# Ref_Supply_Unit.net
KiCad netlist of a schematic drawn in Altium Designer
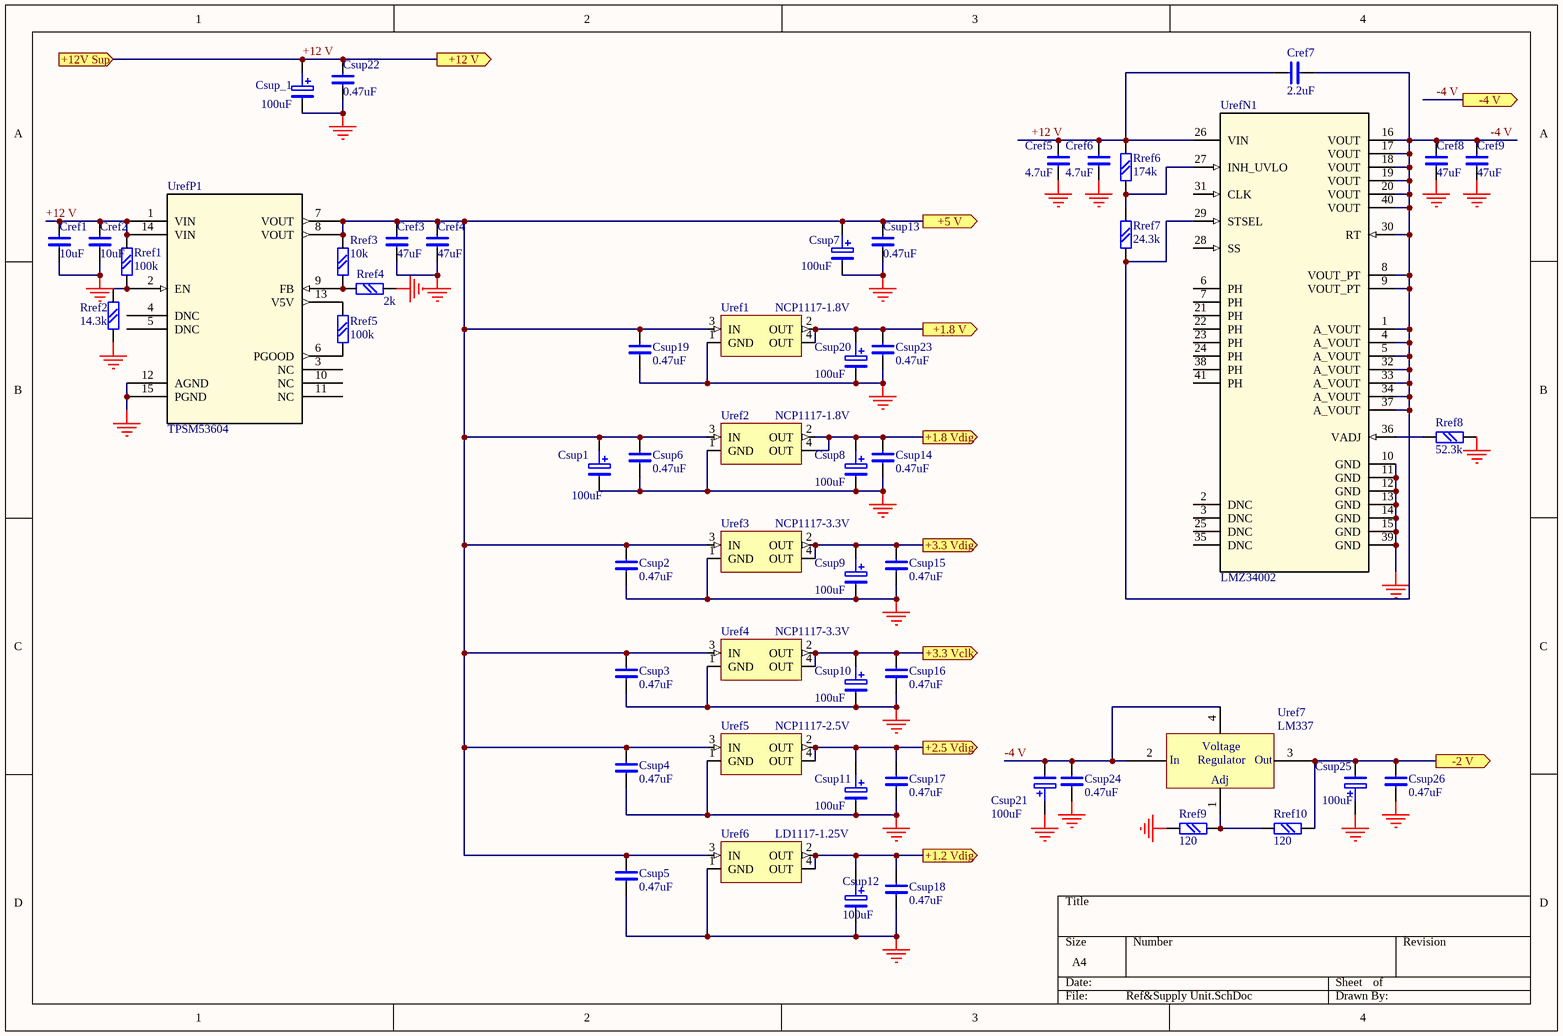
[diagram p0: Ref&Supply Unit.SchDoc]

(export (version "E")
  (design (tool "Eeschema 10.0.6"))
  (components
    (comp (ref "Cref1") (value "10uF") (footprint "CHIP1206") (libsource (lib "*") (part "C")))
    (comp (ref "Cref2") (value "10uF") (footprint "CHIP1206") (libsource (lib "*") (part "C")))
    (comp (ref "Cref3") (value "47uF") (footprint "CHIP1206") (libsource (lib "*") (part "C")))
    (comp (ref "Cref4") (value "47uF") (footprint "CHIP1206") (libsource (lib "*") (part "C")))
    (comp (ref "Cref5") (value "4.7uF") (footprint "chip0805") (libsource (lib "*") (part "C")))
    (comp (ref "Cref6") (value "4.7uF") (footprint "chip0805") (libsource (lib "*") (part "C")))
    (comp (ref "Cref7") (value "2.2uF") (footprint "chip0805") (libsource (lib "*") (part "C")))
    (comp (ref "Cref8") (value "47uF") (footprint "chip1206") (libsource (lib "*") (part "C")))
    (comp (ref "Cref9") (value "47uF") (footprint "chip1206") (libsource (lib "*") (part "C")))
    (comp (ref "Csup1") (value "100uF") (footprint "CEL-SMD300") (libsource (lib "*") (part "C POL")))
    (comp (ref "Csup2") (value "0.47uF") (footprint "chip0603") (libsource (lib "*") (part "C")))
    (comp (ref "Csup3") (value "0.47uF") (footprint "chip0603") (libsource (lib "*") (part "C")))
    (comp (ref "Csup4") (value "0.47uF") (footprint "chip0603") (libsource (lib "*") (part "C")))
    (comp (ref "Csup5") (value "0.47uF") (footprint "chip0603") (libsource (lib "*") (part "C")))
    (comp (ref "Csup6") (value "0.47uF") (footprint "chip0603") (libsource (lib "*") (part "C")))
    (comp (ref "Csup7") (value "100uF") (footprint "CEL-SMD300") (libsource (lib "*") (part "C POL")))
    (comp (ref "Csup8") (value "100uF") (footprint "CEL-SMD300") (libsource (lib "*") (part "C POL")))
    (comp (ref "Csup9") (value "100uF") (footprint "CEL-SMD300") (libsource (lib "*") (part "C POL")))
    (comp (ref "Csup10") (value "100uF") (footprint "CEL-SMD300") (libsource (lib "*") (part "C POL")))
    (comp (ref "Csup11") (value "100uF") (footprint "CEL-SMD300") (libsource (lib "*") (part "C POL")))
    (comp (ref "Csup12") (value "100uF") (footprint "CEL-SMD300") (libsource (lib "*") (part "C POL")))
    (comp (ref "Csup13") (value "0.47uF") (footprint "chip0603") (libsource (lib "*") (part "C")))
    (comp (ref "Csup14") (value "0.47uF") (footprint "chip0603") (libsource (lib "*") (part "C")))
    (comp (ref "Csup15") (value "0.47uF") (footprint "chip0603") (libsource (lib "*") (part "C")))
    (comp (ref "Csup16") (value "0.47uF") (footprint "chip0603") (libsource (lib "*") (part "C")))
    (comp (ref "Csup17") (value "0.47uF") (footprint "chip0603") (libsource (lib "*") (part "C")))
    (comp (ref "Csup18") (value "0.47uF") (footprint "chip0603") (libsource (lib "*") (part "C")))
    (comp (ref "Csup19") (value "0.47uF") (footprint "chip0603") (libsource (lib "*") (part "C")))
    (comp (ref "Csup20") (value "100uF") (footprint "CEL-SMD300") (libsource (lib "*") (part "C POL")))
    (comp (ref "Csup21") (value "100uF") (footprint "CEL-SMD300") (libsource (lib "*") (part "C POL")))
    (comp (ref "Csup22") (value "0.47uF") (footprint "chip0603") (libsource (lib "*") (part "C")))
    (comp (ref "Csup23") (value "0.47uF") (footprint "chip0603") (libsource (lib "*") (part "C")))
    (comp (ref "Csup24") (value "0.47uF") (footprint "chip0603") (libsource (lib "*") (part "C")))
    (comp (ref "Csup25") (value "100uF") (footprint "CEL-SMD300") (libsource (lib "*") (part "C POL")))
    (comp (ref "Csup26") (value "0.47uF") (footprint "chip0603") (libsource (lib "*") (part "C")))
    (comp (ref "Csup_1") (value "100uF") (footprint "CEL-SMD300") (libsource (lib "*") (part "C POL")))
    (comp (ref "Rref1") (value "100k") (footprint "chip0603") (libsource (lib "*") (part "MLT")))
    (comp (ref "Rref2") (value "14.3k") (footprint "chip0603") (libsource (lib "*") (part "MLT")))
    (comp (ref "Rref3") (value "10k") (footprint "chip0603") (libsource (lib "*") (part "MLT")))
    (comp (ref "Rref4") (value "2k") (footprint "chip0603") (libsource (lib "*") (part "MLT")))
    (comp (ref "Rref5") (value "100k") (footprint "chip0603") (libsource (lib "*") (part "MLT")))
    (comp (ref "Rref6") (value "174k") (footprint "chip0603") (libsource (lib "*") (part "MLT")))
    (comp (ref "Rref7") (value "24.3k") (footprint "chip0603") (libsource (lib "*") (part "MLT")))
    (comp (ref "Rref8") (value "52.3k") (footprint "chip0603") (libsource (lib "*") (part "MLT")))
    (comp (ref "Rref9") (value "120") (footprint "chip0603") (libsource (lib "*") (part "MLT")))
    (comp (ref "Rref10") (value "120") (footprint "chip0603") (libsource (lib "*") (part "MLT")))
    (comp (ref "Uref1")
      (value "NCP1117-1.8V")
      (footprint "369A-13")
      (libsource (lib "vAnalog") (part "NCP1117-3.3V"))
    )
    (comp (ref "Uref2")
      (value "NCP1117-1.8V")
      (footprint "369A-13")
      (libsource (lib "vAnalog") (part "NCP1117-3.3V"))
    )
    (comp (ref "Uref3")
      (value "NCP1117-3.3V")
      (footprint "369A-13")
      (libsource (lib "vAnalog") (part "NCP1117-3.3V"))
    )
    (comp (ref "Uref4")
      (value "NCP1117-3.3V")
      (footprint "369A-13")
      (libsource (lib "vAnalog") (part "NCP1117-3.3V"))
    )
    (comp (ref "Uref5")
      (value "NCP1117-2.5V")
      (footprint "369A-13")
      (libsource (lib "vAnalog") (part "NCP1117-3.3V"))
    )
    (comp (ref "Uref6")
      (value "LD1117-1.25V")
      (footprint "369A-13")
      (libsource (lib "vAnalog") (part "NCP1117-3.3V"))
    )
    (comp (ref "Uref7")
      (value "LM337")
      (footprint "SOT-223")
      (description "Adjustable Negative Volage Regulators")
      (libsource (lib "Backup of Mylib") (part "LM337"))
    )
    (comp (ref "UrefN1")
      (value "LMZ34002")
      (footprint "B1QFN-41")
      (libsource (lib "vAnalog") (part "LMZ34002"))
    )
    (comp (ref "UrefP1")
      (value "TPSM53604")
      (footprint "B3QFN-15")
      (libsource (lib "vAnalog") (part "TPSM53604"))
    )
  )
  (nets
    (net (code "1") (name "/+1.2 Vdig") (class "Default")
      (node (ref "Csup12") (pin "+") (pinfunction "+_+") (pintype "passive"))
      (node (ref "Csup18") (pin "1") (pinfunction "1_1") (pintype "passive"))
      (node (ref "Uref6") (pin "2") (pinfunction "OUT_2") (pintype "output"))
      (node (ref "Uref6") (pin "4") (pinfunction "OUT_4") (pintype "passive"))
    )
    (net (code "2") (name "/+1.8 V") (class "Default")
      (node (ref "Csup20") (pin "+") (pinfunction "+_+") (pintype "passive"))
      (node (ref "Csup23") (pin "1") (pinfunction "1_1") (pintype "passive"))
      (node (ref "Uref1") (pin "2") (pinfunction "OUT_2") (pintype "output"))
      (node (ref "Uref1") (pin "4") (pinfunction "OUT_4") (pintype "passive"))
    )
    (net (code "3") (name "/+1.8 Vdig") (class "Default")
      (node (ref "Csup14") (pin "1") (pinfunction "1_1") (pintype "passive"))
      (node (ref "Csup8") (pin "+") (pinfunction "+_+") (pintype "passive"))
      (node (ref "Uref2") (pin "2") (pinfunction "OUT_2") (pintype "output"))
      (node (ref "Uref2") (pin "4") (pinfunction "OUT_4") (pintype "passive"))
    )
    (net (code "4") (name "/+2.5 Vdig") (class "Default")
      (node (ref "Csup11") (pin "+") (pinfunction "+_+") (pintype "passive"))
      (node (ref "Csup17") (pin "1") (pinfunction "1_1") (pintype "passive"))
      (node (ref "Uref5") (pin "2") (pinfunction "OUT_2") (pintype "output"))
      (node (ref "Uref5") (pin "4") (pinfunction "OUT_4") (pintype "passive"))
    )
    (net (code "5") (name "/+3.3 Vclk") (class "Default")
      (node (ref "Csup10") (pin "+") (pinfunction "+_+") (pintype "passive"))
      (node (ref "Csup16") (pin "1") (pinfunction "1_1") (pintype "passive"))
      (node (ref "Uref4") (pin "2") (pinfunction "OUT_2") (pintype "output"))
      (node (ref "Uref4") (pin "4") (pinfunction "OUT_4") (pintype "passive"))
    )
    (net (code "6") (name "/+3.3 Vdig") (class "Default")
      (node (ref "Csup15") (pin "1") (pinfunction "1_1") (pintype "passive"))
      (node (ref "Csup9") (pin "+") (pinfunction "+_+") (pintype "passive"))
      (node (ref "Uref3") (pin "2") (pinfunction "OUT_2") (pintype "output"))
      (node (ref "Uref3") (pin "4") (pinfunction "OUT_4") (pintype "passive"))
    )
    (net (code "7") (name "/+5 V") (class "Default")
      (node (ref "Cref3") (pin "1") (pinfunction "1_1") (pintype "passive"))
      (node (ref "Cref4") (pin "1") (pinfunction "1_1") (pintype "passive"))
      (node (ref "Csup1") (pin "+") (pinfunction "+_+") (pintype "passive"))
      (node (ref "Csup13") (pin "1") (pinfunction "1_1") (pintype "passive"))
      (node (ref "Csup19") (pin "1") (pinfunction "1_1") (pintype "passive"))
      (node (ref "Csup2") (pin "1") (pinfunction "1_1") (pintype "passive"))
      (node (ref "Csup3") (pin "1") (pinfunction "1_1") (pintype "passive"))
      (node (ref "Csup4") (pin "1") (pinfunction "1_1") (pintype "passive"))
      (node (ref "Csup5") (pin "1") (pinfunction "1_1") (pintype "passive"))
      (node (ref "Csup6") (pin "1") (pinfunction "1_1") (pintype "passive"))
      (node (ref "Csup7") (pin "+") (pinfunction "+_+") (pintype "passive"))
      (node (ref "Rref3") (pin "2") (pinfunction "2_2") (pintype "passive"))
      (node (ref "Uref1") (pin "3") (pinfunction "IN_3") (pintype "input"))
      (node (ref "Uref2") (pin "3") (pinfunction "IN_3") (pintype "input"))
      (node (ref "Uref3") (pin "3") (pinfunction "IN_3") (pintype "input"))
      (node (ref "Uref4") (pin "3") (pinfunction "IN_3") (pintype "input"))
      (node (ref "Uref5") (pin "3") (pinfunction "IN_3") (pintype "input"))
      (node (ref "Uref6") (pin "3") (pinfunction "IN_3") (pintype "input"))
      (node (ref "UrefP1") (pin "7") (pinfunction "VOUT_7") (pintype "output"))
      (node (ref "UrefP1") (pin "8") (pinfunction "VOUT_8") (pintype "output"))
    )
    (net (code "8") (name "/+12 V") (class "Default")
      (node (ref "Cref1") (pin "1") (pinfunction "1_1") (pintype "passive"))
      (node (ref "Cref2") (pin "1") (pinfunction "1_1") (pintype "passive"))
      (node (ref "Cref5") (pin "1") (pinfunction "1_1") (pintype "passive"))
      (node (ref "Cref6") (pin "1") (pinfunction "1_1") (pintype "passive"))
      (node (ref "Cref7") (pin "1") (pinfunction "1_1") (pintype "passive"))
      (node (ref "Csup22") (pin "1") (pinfunction "1_1") (pintype "passive"))
      (node (ref "Csup_1") (pin "+") (pinfunction "+_+") (pintype "passive"))
      (node (ref "Rref1") (pin "2") (pinfunction "2_2") (pintype "passive"))
      (node (ref "Rref6") (pin "2") (pinfunction "2_2") (pintype "passive"))
      (node (ref "UrefN1") (pin "26") (pinfunction "VIN_26") (pintype "power_in"))
      (node (ref "UrefP1") (pin "1") (pinfunction "VIN_1") (pintype "power_in"))
      (node (ref "UrefP1") (pin "14") (pinfunction "VIN_14") (pintype "power_in"))
    )
    (net (code "9") (name "/-2 V") (class "Default")
      (node (ref "Csup25") (pin "-") (pinfunction "-_-") (pintype "passive"))
      (node (ref "Csup26") (pin "1") (pinfunction "1_1") (pintype "passive"))
      (node (ref "Rref10") (pin "1") (pinfunction "1_1") (pintype "passive"))
      (node (ref "Uref7") (pin "3") (pinfunction "Out_3") (pintype "passive"))
    )
    (net (code "10") (name "/-4 V") (class "Default")
      (node (ref "Cref7") (pin "2") (pinfunction "2_2") (pintype "passive"))
      (node (ref "Cref8") (pin "1") (pinfunction "1_1") (pintype "passive"))
      (node (ref "Cref9") (pin "1") (pinfunction "1_1") (pintype "passive"))
      (node (ref "Csup21") (pin "-") (pinfunction "-_-") (pintype "passive"))
      (node (ref "Csup24") (pin "1") (pinfunction "1_1") (pintype "passive"))
      (node (ref "Rref7") (pin "1") (pinfunction "1_1") (pintype "passive"))
      (node (ref "Uref7") (pin "2") (pinfunction "In_2") (pintype "passive"))
      (node (ref "Uref7") (pin "4") (pinfunction "Substrate_4") (pintype "passive"))
      (node (ref "UrefN1") (pin "1") (pinfunction "A_VOUT_1") (pintype "power_in"))
      (node (ref "UrefN1") (pin "16") (pinfunction "VOUT_16") (pintype "power_in"))
      (node (ref "UrefN1") (pin "17") (pinfunction "VOUT_17") (pintype "power_in"))
      (node (ref "UrefN1") (pin "18") (pinfunction "VOUT_18") (pintype "power_in"))
      (node (ref "UrefN1") (pin "19") (pinfunction "VOUT_19") (pintype "power_in"))
      (node (ref "UrefN1") (pin "20") (pinfunction "VOUT_20") (pintype "power_in"))
      (node (ref "UrefN1") (pin "29") (pinfunction "STSEL_29") (pintype "input"))
      (node (ref "UrefN1") (pin "30") (pinfunction "RT_30") (pintype "input"))
      (node (ref "UrefN1") (pin "32") (pinfunction "A_VOUT_32") (pintype "power_in"))
      (node (ref "UrefN1") (pin "33") (pinfunction "A_VOUT_33") (pintype "power_in"))
      (node (ref "UrefN1") (pin "34") (pinfunction "A_VOUT_34") (pintype "power_in"))
      (node (ref "UrefN1") (pin "37") (pinfunction "A_VOUT_37") (pintype "power_in"))
      (node (ref "UrefN1") (pin "4") (pinfunction "A_VOUT_4") (pintype "power_in"))
      (node (ref "UrefN1") (pin "40") (pinfunction "VOUT_40") (pintype "power_in"))
      (node (ref "UrefN1") (pin "5") (pinfunction "A_VOUT_5") (pintype "power_in"))
      (node (ref "UrefN1") (pin "8") (pinfunction "VOUT_PT_8") (pintype "passive"))
      (node (ref "UrefN1") (pin "9") (pinfunction "VOUT_PT_9") (pintype "passive"))
    )
    (net (code "11") (name "GND") (class "Default")
      (node (ref "Cref1") (pin "2") (pinfunction "2_2") (pintype "passive"))
      (node (ref "Cref2") (pin "2") (pinfunction "2_2") (pintype "passive"))
      (node (ref "Cref3") (pin "2") (pinfunction "2_2") (pintype "passive"))
      (node (ref "Cref4") (pin "2") (pinfunction "2_2") (pintype "passive"))
      (node (ref "Cref5") (pin "2") (pinfunction "2_2") (pintype "passive"))
      (node (ref "Cref6") (pin "2") (pinfunction "2_2") (pintype "passive"))
      (node (ref "Cref8") (pin "2") (pinfunction "2_2") (pintype "passive"))
      (node (ref "Cref9") (pin "2") (pinfunction "2_2") (pintype "passive"))
      (node (ref "Csup1") (pin "-") (pinfunction "-_-") (pintype "passive"))
      (node (ref "Csup10") (pin "-") (pinfunction "-_-") (pintype "passive"))
      (node (ref "Csup11") (pin "-") (pinfunction "-_-") (pintype "passive"))
      (node (ref "Csup12") (pin "-") (pinfunction "-_-") (pintype "passive"))
      (node (ref "Csup13") (pin "2") (pinfunction "2_2") (pintype "passive"))
      (node (ref "Csup14") (pin "2") (pinfunction "2_2") (pintype "passive"))
      (node (ref "Csup15") (pin "2") (pinfunction "2_2") (pintype "passive"))
      (node (ref "Csup16") (pin "2") (pinfunction "2_2") (pintype "passive"))
      (node (ref "Csup17") (pin "2") (pinfunction "2_2") (pintype "passive"))
      (node (ref "Csup18") (pin "2") (pinfunction "2_2") (pintype "passive"))
      (node (ref "Csup19") (pin "2") (pinfunction "2_2") (pintype "passive"))
      (node (ref "Csup2") (pin "2") (pinfunction "2_2") (pintype "passive"))
      (node (ref "Csup20") (pin "-") (pinfunction "-_-") (pintype "passive"))
      (node (ref "Csup21") (pin "+") (pinfunction "+_+") (pintype "passive"))
      (node (ref "Csup22") (pin "2") (pinfunction "2_2") (pintype "passive"))
      (node (ref "Csup23") (pin "2") (pinfunction "2_2") (pintype "passive"))
      (node (ref "Csup24") (pin "2") (pinfunction "2_2") (pintype "passive"))
      (node (ref "Csup25") (pin "+") (pinfunction "+_+") (pintype "passive"))
      (node (ref "Csup26") (pin "2") (pinfunction "2_2") (pintype "passive"))
      (node (ref "Csup3") (pin "2") (pinfunction "2_2") (pintype "passive"))
      (node (ref "Csup4") (pin "2") (pinfunction "2_2") (pintype "passive"))
      (node (ref "Csup5") (pin "2") (pinfunction "2_2") (pintype "passive"))
      (node (ref "Csup6") (pin "2") (pinfunction "2_2") (pintype "passive"))
      (node (ref "Csup7") (pin "-") (pinfunction "-_-") (pintype "passive"))
      (node (ref "Csup8") (pin "-") (pinfunction "-_-") (pintype "passive"))
      (node (ref "Csup9") (pin "-") (pinfunction "-_-") (pintype "passive"))
      (node (ref "Csup_1") (pin "-") (pinfunction "-_-") (pintype "passive"))
      (node (ref "Rref2") (pin "1") (pinfunction "1_1") (pintype "passive"))
      (node (ref "Rref4") (pin "1") (pinfunction "1_1") (pintype "passive"))
      (node (ref "Rref8") (pin "2") (pinfunction "2_2") (pintype "passive"))
      (node (ref "Rref9") (pin "2") (pinfunction "2_2") (pintype "passive"))
      (node (ref "Uref1") (pin "1") (pinfunction "GND_1") (pintype "power_in"))
      (node (ref "Uref2") (pin "1") (pinfunction "GND_1") (pintype "power_in"))
      (node (ref "Uref3") (pin "1") (pinfunction "GND_1") (pintype "power_in"))
      (node (ref "Uref4") (pin "1") (pinfunction "GND_1") (pintype "power_in"))
      (node (ref "Uref5") (pin "1") (pinfunction "GND_1") (pintype "power_in"))
      (node (ref "Uref6") (pin "1") (pinfunction "GND_1") (pintype "power_in"))
      (node (ref "UrefN1") (pin "10") (pinfunction "GND_10") (pintype "power_in"))
      (node (ref "UrefN1") (pin "11") (pinfunction "GND_11") (pintype "power_in"))
      (node (ref "UrefN1") (pin "12") (pinfunction "GND_12") (pintype "power_in"))
      (node (ref "UrefN1") (pin "13") (pinfunction "GND_13") (pintype "power_in"))
      (node (ref "UrefN1") (pin "14") (pinfunction "GND_14") (pintype "power_in"))
      (node (ref "UrefN1") (pin "15") (pinfunction "GND_15") (pintype "power_in"))
      (node (ref "UrefN1") (pin "39") (pinfunction "GND_39") (pintype "power_in"))
      (node (ref "UrefP1") (pin "12") (pinfunction "AGND_12") (pintype "passive"))
      (node (ref "UrefP1") (pin "15") (pinfunction "PGND_15") (pintype "passive"))
    )
    (net (code "12") (name "Net-(Uref7-ADJ)") (class "Default")
      (node (ref "Rref10") (pin "2") (pinfunction "2_2") (pintype "passive"))
      (node (ref "Rref9") (pin "1") (pinfunction "1_1") (pintype "passive"))
      (node (ref "Uref7") (pin "1") (pinfunction "ADJ_1") (pintype "power_in"))
    )
    (net (code "13") (name "Net-(UrefN1-INH_UVLO)") (class "Default")
      (node (ref "Rref6") (pin "1") (pinfunction "1_1") (pintype "passive"))
      (node (ref "Rref7") (pin "2") (pinfunction "2_2") (pintype "passive"))
      (node (ref "UrefN1") (pin "27") (pinfunction "INH_UVLO_27") (pintype "input"))
    )
    (net (code "14") (name "Net-(UrefN1-VADJ)") (class "Default")
      (node (ref "Rref8") (pin "1") (pinfunction "1_1") (pintype "passive"))
      (node (ref "UrefN1") (pin "36") (pinfunction "VADJ_36") (pintype "input"))
    )
    (net (code "15") (name "Net-(UrefP1-EN)") (class "Default")
      (node (ref "Rref1") (pin "1") (pinfunction "1_1") (pintype "passive"))
      (node (ref "Rref2") (pin "2") (pinfunction "2_2") (pintype "passive"))
      (node (ref "UrefP1") (pin "2") (pinfunction "EN_2") (pintype "input"))
    )
    (net (code "16") (name "Net-(UrefP1-FB)") (class "Default")
      (node (ref "Rref3") (pin "1") (pinfunction "1_1") (pintype "passive"))
      (node (ref "Rref4") (pin "2") (pinfunction "2_2") (pintype "passive"))
      (node (ref "UrefP1") (pin "9") (pinfunction "FB_9") (pintype "input"))
    )
    (net (code "17") (name "Net-(UrefP1-PGOOD)") (class "Default")
      (node (ref "Rref5") (pin "1") (pinfunction "1_1") (pintype "passive"))
      (node (ref "UrefP1") (pin "6") (pinfunction "PGOOD_6") (pintype "output"))
    )
    (net (code "18") (name "Net-(UrefP1-V5V)") (class "Default")
      (node (ref "Rref5") (pin "2") (pinfunction "2_2") (pintype "passive"))
      (node (ref "UrefP1") (pin "13") (pinfunction "V5V_13") (pintype "output"))
    )
    (net (code "19") (name "unconnected-(UrefN1-CLK-Pad31)") (class "Default")
      (node (ref "UrefN1") (pin "31") (pinfunction "CLK_31") (pintype "input"))
    )
    (net (code "20") (name "unconnected-(UrefN1-DNC-Pad2)") (class "Default")
      (node (ref "UrefN1") (pin "2") (pinfunction "DNC_2") (pintype "passive"))
    )
    (net (code "21") (name "unconnected-(UrefN1-DNC-Pad3)") (class "Default")
      (node (ref "UrefN1") (pin "3") (pinfunction "DNC_3") (pintype "passive"))
    )
    (net (code "22") (name "unconnected-(UrefN1-DNC-Pad25)") (class "Default")
      (node (ref "UrefN1") (pin "25") (pinfunction "DNC_25") (pintype "passive"))
    )
    (net (code "23") (name "unconnected-(UrefN1-DNC-Pad35)") (class "Default")
      (node (ref "UrefN1") (pin "35") (pinfunction "DNC_35") (pintype "passive"))
    )
    (net (code "24") (name "unconnected-(UrefN1-PH-Pad6)") (class "Default")
      (node (ref "UrefN1") (pin "6") (pinfunction "PH_6") (pintype "passive"))
    )
    (net (code "25") (name "unconnected-(UrefN1-PH-Pad7)") (class "Default")
      (node (ref "UrefN1") (pin "7") (pinfunction "PH_7") (pintype "passive"))
    )
    (net (code "26") (name "unconnected-(UrefN1-PH-Pad21)") (class "Default")
      (node (ref "UrefN1") (pin "21") (pinfunction "PH_21") (pintype "passive"))
    )
    (net (code "27") (name "unconnected-(UrefN1-PH-Pad22)") (class "Default")
      (node (ref "UrefN1") (pin "22") (pinfunction "PH_22") (pintype "passive"))
    )
    (net (code "28") (name "unconnected-(UrefN1-PH-Pad23)") (class "Default")
      (node (ref "UrefN1") (pin "23") (pinfunction "PH_23") (pintype "passive"))
    )
    (net (code "29") (name "unconnected-(UrefN1-PH-Pad24)") (class "Default")
      (node (ref "UrefN1") (pin "24") (pinfunction "PH_24") (pintype "passive"))
    )
    (net (code "30") (name "unconnected-(UrefN1-PH-Pad38)") (class "Default")
      (node (ref "UrefN1") (pin "38") (pinfunction "PH_38") (pintype "passive"))
    )
    (net (code "31") (name "unconnected-(UrefN1-PH-Pad41)") (class "Default")
      (node (ref "UrefN1") (pin "41") (pinfunction "PH_41") (pintype "passive"))
    )
    (net (code "32") (name "unconnected-(UrefN1-SS-Pad28)") (class "Default")
      (node (ref "UrefN1") (pin "28") (pinfunction "SS_28") (pintype "input"))
    )
    (net (code "33") (name "unconnected-(UrefP1-DNC-Pad4)") (class "Default")
      (node (ref "UrefP1") (pin "4") (pinfunction "DNC_4") (pintype "passive"))
    )
    (net (code "34") (name "unconnected-(UrefP1-DNC-Pad5)") (class "Default")
      (node (ref "UrefP1") (pin "5") (pinfunction "DNC_5") (pintype "passive"))
    )
    (net (code "35") (name "unconnected-(UrefP1-NC-Pad3)") (class "Default")
      (node (ref "UrefP1") (pin "3") (pinfunction "NC_3") (pintype "passive"))
    )
    (net (code "36") (name "unconnected-(UrefP1-NC-Pad10)") (class "Default")
      (node (ref "UrefP1") (pin "10") (pinfunction "NC_10") (pintype "passive"))
    )
    (net (code "37") (name "unconnected-(UrefP1-NC-Pad11)") (class "Default")
      (node (ref "UrefP1") (pin "11") (pinfunction "NC_11") (pintype "passive"))
    )
  )
)
